# ProtectionAndShunt.net
KiCad netlist of a schematic drawn in Altium Designer
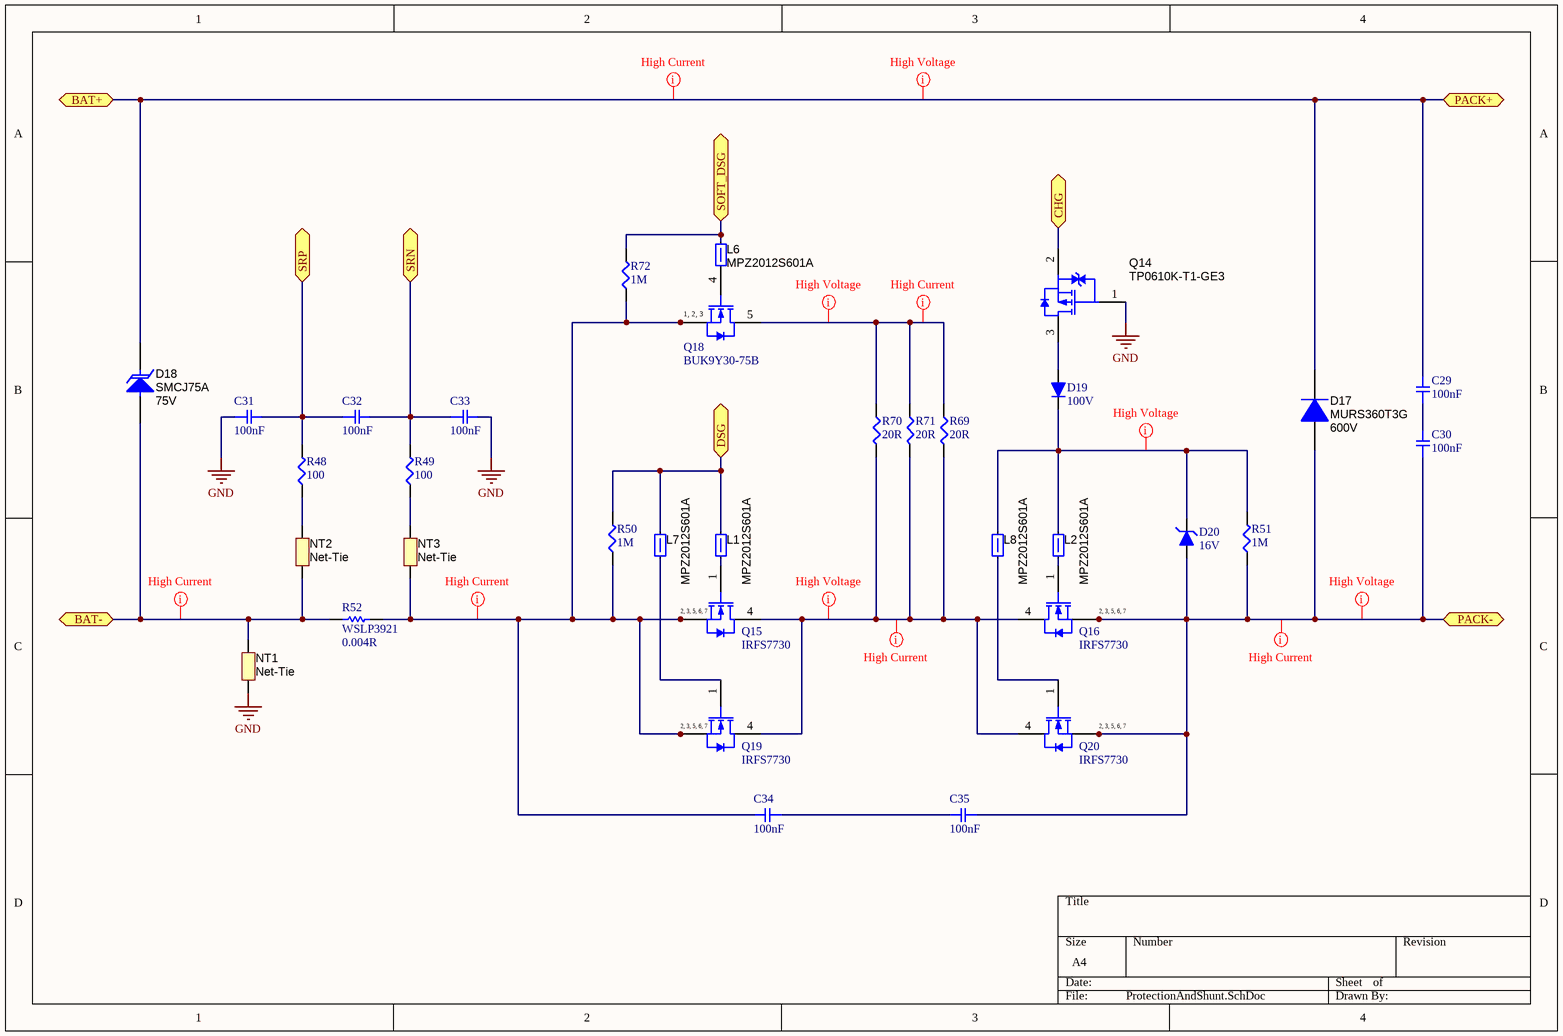
[diagram p0: ProtectionAndShunt.SchDoc]

(export (version "E")
  (design (tool "Eeschema 10.0.6"))
  (components
    (comp (ref "C29")
      (value "100nF")
      (footprint "SMD-0603C")
      (description "CAP CER 0.1UF 16V X7R 0603")
      (fields
        (field (name "DIGI-KEY PART NUMBER") "490-5796-1-ND")
        (field (name "PART NUMBER") "GCJ188R71C104KA01D")
      )
      (libsource (lib "capacitor_murata_0603") (part "GCJ188R71C104KA01D"))
    )
    (comp (ref "C30")
      (value "100nF")
      (footprint "SMD-0603C")
      (description "CAP CER 0.1UF 16V X7R 0603")
      (fields
        (field (name "DIGI-KEY PART NUMBER") "490-5796-1-ND")
        (field (name "PART NUMBER") "GCJ188R71C104KA01D")
      )
      (libsource (lib "capacitor_murata_0603") (part "GCJ188R71C104KA01D"))
    )
    (comp (ref "C31")
      (value "100nF")
      (footprint "SMD-0603C")
      (description "CAP CER 0.1UF 16V X7R 0603")
      (fields
        (field (name "DIGI-KEY PART NUMBER") "490-5796-1-ND")
        (field (name "PART NUMBER") "GCJ188R71C104KA01D")
      )
      (libsource (lib "capacitor_murata_0603") (part "GCJ188R71C104KA01D"))
    )
    (comp (ref "C32")
      (value "100nF")
      (footprint "SMD-0603C")
      (description "CAP CER 0.1UF 16V X7R 0603")
      (fields
        (field (name "DIGI-KEY PART NUMBER") "490-5796-1-ND")
        (field (name "PART NUMBER") "GCJ188R71C104KA01D")
      )
      (libsource (lib "capacitor_murata_0603") (part "GCJ188R71C104KA01D"))
    )
    (comp (ref "C33")
      (value "100nF")
      (footprint "SMD-0603C")
      (description "CAP CER 0.1UF 16V X7R 0603")
      (fields
        (field (name "DIGI-KEY PART NUMBER") "490-5796-1-ND")
        (field (name "PART NUMBER") "GCJ188R71C104KA01D")
      )
      (libsource (lib "capacitor_murata_0603") (part "GCJ188R71C104KA01D"))
    )
    (comp (ref "C34")
      (value "100nF")
      (footprint "SMD-0603C")
      (description "CAP CER 0.1UF 16V X7R 0603")
      (fields
        (field (name "DIGI-KEY PART NUMBER") "490-5796-1-ND")
        (field (name "PART NUMBER") "GCJ188R71C104KA01D")
      )
      (libsource (lib "capacitor_murata_0603") (part "GCJ188R71C104KA01D"))
    )
    (comp (ref "C35")
      (value "100nF")
      (footprint "SMD-0603C")
      (description "CAP CER 0.1UF 16V X7R 0603")
      (fields
        (field (name "DIGI-KEY PART NUMBER") "490-5796-1-ND")
        (field (name "PART NUMBER") "GCJ188R71C104KA01D")
      )
      (libsource (lib "capacitor_murata_0603") (part "GCJ188R71C104KA01D"))
    )
    (comp (ref "D17")
      (value "MURS360T3G")
      (footprint "SMC")
      (description "Diode, Ultrafast, 600V, 3A, SMC")
      (fields
        (field (name "MANUFACTURER") "ON Semiconductor")
        (field (name "ALTIUM_VALUE") "600V")
        (field (name "PUBLISHER") "Texas Instruments")
      )
      (libsource (lib "Components") (part "MURS360T3G"))
    )
    (comp (ref "D18")
      (value "SMCJ75A")
      (footprint "SMC")
      (description "Diode, TVS, Uni, 75V, 1500W, SMC")
      (fields
        (field (name "MANUFACTURER") "Fairchild Semiconductor")
        (field (name "ALTIUM_VALUE") "75V")
        (field (name "PUBLISHER") "Texas Instruments")
      )
      (libsource (lib "Components") (part "SMCJ75A"))
    )
    (comp (ref "D19")
      (value "100V")
      (footprint "SOD-323")
      (description "Diode")
      (libsource (lib "Components") (part "DIODE"))
    )
    (comp (ref "D20")
      (value "16V")
      (footprint "SOD-323")
      (description "Zener Diode 16V")
      (libsource (lib "Components") (part "ZENER_16V"))
    )
    (comp (ref "L1")
      (value "MPZ2012S601A")
      (footprint "SMD-0805-RES")
      (description "Ferrite Bead")
      (fields
        (field (name "PARTNUMBER") "BLM18SG221TN1D")
        (field (name "MANUFACTURER") "MuRata")
        (field (name "PUBLISHER") "Texas Instruments")
      )
      (libsource (lib "") (part "BLM18SG221TN1D_1"))
    )
    (comp (ref "L2")
      (value "MPZ2012S601A")
      (footprint "SMD-0805-RES")
      (description "Ferrite Bead")
      (fields
        (field (name "PARTNUMBER") "BLM18SG221TN1D")
        (field (name "MANUFACTURER") "MuRata")
        (field (name "PUBLISHER") "Texas Instruments")
      )
      (libsource (lib "Components") (part "BLM18SG221TN1D"))
    )
    (comp (ref "L6")
      (value "MPZ2012S601A")
      (footprint "SMD-0805-RES")
      (description "Ferrite Bead")
      (fields
        (field (name "PARTNUMBER") "BLM18SG221TN1D")
        (field (name "MANUFACTURER") "MuRata")
        (field (name "PUBLISHER") "Texas Instruments")
      )
      (libsource (lib "") (part "BLM18SG221TN1D_1"))
    )
    (comp (ref "L7")
      (value "MPZ2012S601A")
      (footprint "SMD-0805-RES")
      (description "Ferrite Bead")
      (fields
        (field (name "PARTNUMBER") "BLM18SG221TN1D")
        (field (name "MANUFACTURER") "MuRata")
        (field (name "PUBLISHER") "Texas Instruments")
      )
      (libsource (lib "") (part "BLM18SG221TN1D_1"))
    )
    (comp (ref "L8")
      (value "MPZ2012S601A")
      (footprint "SMD-0805-RES")
      (description "Ferrite Bead")
      (fields
        (field (name "PARTNUMBER") "BLM18SG221TN1D")
        (field (name "MANUFACTURER") "MuRata")
        (field (name "PUBLISHER") "Texas Instruments")
      )
      (libsource (lib "Components") (part "BLM18SG221TN1D"))
    )
    (comp (ref "NT1")
      (value "Net-Tie")
      (footprint "Net-Tie_10mil")
      (description "Single point connection between nets.")
      (fields (field (name "SYMBOLCREATOR") "codlsc") (field (name "PUBLISHER") "Texas Instruments"))
      (libsource (lib "Components") (part "Net-Tie"))
    )
    (comp (ref "NT2")
      (value "Net-Tie")
      (footprint "Net-Tie_10mil")
      (description "Single point connection between nets.")
      (fields (field (name "SYMBOLCREATOR") "codlsc") (field (name "PUBLISHER") "Texas Instruments"))
      (libsource (lib "Components") (part "Net-Tie"))
    )
    (comp (ref "NT3")
      (value "Net-Tie")
      (footprint "Net-Tie_10mil")
      (description "Single point connection between nets.")
      (fields (field (name "SYMBOLCREATOR") "codlsc") (field (name "PUBLISHER") "Texas Instruments"))
      (libsource (lib "Components") (part "Net-Tie"))
    )
    (comp (ref "Q14")
      (value "TP0610K-T1-GE3")
      (footprint "SOT23-3")
      (description "MOSFET, P-CH, -60 V, -0.185 A, SOT-23")
      (fields
        (field (name "MANUFACTURER") "Vishay-Siliconix")
        (field (name "SYMBOLCREATOR") "a0411947")
        (field (name "PUBLISHER") "Texas Instruments")
      )
      (libsource (lib "Components") (part "TP0610K-T1-GE3"))
    )
    (comp (ref "Q15")
      (value "IRFS7730")
      (footprint "INF-PG-TO263-7-3_N")
      (description "OptiMOS-T Power-Transistor, 40 V VDS, 180 A ID, PG-TO263-7-3, Reel, Green")
      (fields (field (name "MANUFACTURER") "Infineon") (field (name "PARTNUMBER") "IPB180N04S3-02"))
      (libsource (lib "Infineon_Power_MOSFET") (part "IPB180N04S3-02"))
    )
    (comp (ref "Q16")
      (value "IRFS7730")
      (footprint "INF-PG-TO263-7-3_N")
      (description "OptiMOS-T Power-Transistor, 40 V VDS, 180 A ID, PG-TO263-7-3, Reel, Green")
      (fields (field (name "MANUFACTURER") "Infineon") (field (name "PARTNUMBER") "IPB180N04S3-02"))
      (libsource (lib "Infineon_Power_MOSFET") (part "IPB180N04S3-02"))
    )
    (comp (ref "Q18")
      (value "BUK9Y30-75B")
      (footprint "NXP-SOT669_N")
      (description "N-Channel TrenchMOS Logic Level FET, 75 V, 34 A, 5-Pin SOT669, Tape and Reel")
      (fields
        (field (name "MANUFACTURER") "NXP Semiconductors")
        (field (name "PARTNUMBER") "BUK9Y30-75B,115")
      )
      (libsource (lib "NXP Semiconductors Automotive MOSFETs") (part "BUK9Y30-75B,115"))
    )
    (comp (ref "Q19")
      (value "IRFS7730")
      (footprint "INF-PG-TO263-7-3_N")
      (description "OptiMOS-T Power-Transistor, 40 V VDS, 180 A ID, PG-TO263-7-3, Reel, Green")
      (fields (field (name "MANUFACTURER") "Infineon") (field (name "PARTNUMBER") "IPB180N04S3-02"))
      (libsource (lib "Infineon_Power_MOSFET") (part "IPB180N04S3-02"))
    )
    (comp (ref "Q20")
      (value "IRFS7730")
      (footprint "INF-PG-TO263-7-3_N")
      (description "OptiMOS-T Power-Transistor, 40 V VDS, 180 A ID, PG-TO263-7-3, Reel, Green")
      (fields (field (name "MANUFACTURER") "Infineon") (field (name "PARTNUMBER") "IPB180N04S3-02"))
      (libsource (lib "Infineon_Power_MOSFET") (part "IPB180N04S3-02"))
    )
    (comp (ref "R48")
      (value "100")
      (footprint "SMD-0603-RES")
      (description "RES SMD 100 OHM 1% 1/10W 0603")
      (fields (field (name "PART NUMBER") "ERJ-3EKF1000V") (field (name "DIGI-KEY PART NUMBER") "P100HCT-ND"))
      (libsource (lib "Panasonic_ERJ_0603") (part "ERJ-3EKF1000V"))
    )
    (comp (ref "R49")
      (value "100")
      (footprint "SMD-0603-RES")
      (description "RES SMD 100 OHM 1% 1/10W 0603")
      (fields (field (name "PART NUMBER") "ERJ-3EKF1000V") (field (name "DIGI-KEY PART NUMBER") "P100HCT-ND"))
      (libsource (lib "Panasonic_ERJ_0603") (part "ERJ-3EKF1000V"))
    )
    (comp (ref "R50")
      (value "1M")
      (footprint "SMD-0603-RES")
      (description "RES SMD 1M OHM 5% 1/10W 0603")
      (fields
        (field (name "PART NUMBER") "ERJ-3GEYJ105V")
        (field (name "DIGI-KEY PART NUMBER") "P1.0MGCT-ND")
      )
      (libsource (lib "Panasonic_ERJ_0603") (part "ERJ-3GEYJ105V"))
    )
    (comp (ref "R51")
      (value "1M")
      (footprint "SMD-0603-RES")
      (description "RES SMD 1M OHM 5% 1/10W 0603")
      (fields
        (field (name "PART NUMBER") "ERJ-3GEYJ105V")
        (field (name "DIGI-KEY PART NUMBER") "P1.0MGCT-ND")
      )
      (libsource (lib "Panasonic_ERJ_0603") (part "ERJ-3GEYJ105V"))
    )
    (comp (ref "R52")
      (value "WSLP3921")
      (footprint "WSLP3921")
      (fields (field (name "ALTIUM_VALUE") "0.004R"))
      (libsource (lib "Components") (part "WSLP3921"))
    )
    (comp (ref "R69")
      (value "20R")
      (footprint "SMD-1206-RES")
      (description "RES SMD 20 OHM 1% 1/4W 1206")
      (fields
        (field (name "PART NUMBER") "ERJ-8ENF20R0V")
        (field (name "DIGI-KEY PART NUMBER") "P20.0FCT-ND")
      )
      (libsource (lib "Panasonic_ERJ_1206") (part "ERJ-8ENF20R0V"))
    )
    (comp (ref "R70")
      (value "20R")
      (footprint "SMD-1206-RES")
      (description "RES SMD 20 OHM 1% 1/4W 1206")
      (fields
        (field (name "PART NUMBER") "ERJ-8ENF20R0V")
        (field (name "DIGI-KEY PART NUMBER") "P20.0FCT-ND")
      )
      (libsource (lib "Panasonic_ERJ_1206") (part "ERJ-8ENF20R0V"))
    )
    (comp (ref "R71")
      (value "20R")
      (footprint "SMD-1206-RES")
      (description "RES SMD 20 OHM 1% 1/4W 1206")
      (fields
        (field (name "PART NUMBER") "ERJ-8ENF20R0V")
        (field (name "DIGI-KEY PART NUMBER") "P20.0FCT-ND")
      )
      (libsource (lib "Panasonic_ERJ_1206") (part "ERJ-8ENF20R0V"))
    )
    (comp (ref "R72")
      (value "1M")
      (footprint "SMD-0603-RES")
      (description "RES SMD 1M OHM 5% 1/10W 0603")
      (fields
        (field (name "PART NUMBER") "ERJ-3GEYJ105V")
        (field (name "DIGI-KEY PART NUMBER") "P1.0MGCT-ND")
      )
      (libsource (lib "Panasonic_ERJ_0603") (part "ERJ-3GEYJ105V"))
    )
  )
  (nets
    (net (code "1") (name "/BAT+") (class "Default")
      (node (ref "C29") (pin "2") (pinfunction "2_2") (pintype "passive"))
      (node (ref "D17") (pin "1") (pinfunction "K_1") (pintype "passive"))
      (node (ref "D18") (pin "1") (pinfunction "K_1") (pintype "passive"))
    )
    (net (code "2") (name "/BAT-") (class "Default")
      (node (ref "D18") (pin "2") (pinfunction "A_2") (pintype "passive"))
      (node (ref "NT1") (pin "2") (pinfunction "2_2") (pintype "passive"))
      (node (ref "NT2") (pin "1") (pinfunction "1_1") (pintype "passive"))
      (node (ref "R52") (pin "1") (pinfunction "1_1") (pintype "passive"))
    )
    (net (code "3") (name "/CHG") (class "Default")
      (node (ref "Q14") (pin "2") (pinfunction "S_2") (pintype "passive"))
    )
    (net (code "4") (name "/DSG") (class "Default")
      (node (ref "L1") (pin "2") (pinfunction "2_2") (pintype "passive"))
      (node (ref "L7") (pin "2") (pinfunction "2_2") (pintype "passive"))
      (node (ref "R50") (pin "2") (pinfunction "2_2") (pintype "passive"))
    )
    (net (code "5") (name "/PACK-") (class "Default")
      (node (ref "C30") (pin "1") (pinfunction "1_1") (pintype "passive"))
      (node (ref "C35") (pin "1") (pinfunction "1_1") (pintype "passive"))
      (node (ref "D17") (pin "2") (pinfunction "A_2") (pintype "passive"))
      (node (ref "D20") (pin "2") (pinfunction "A_2") (pintype "passive"))
      (node (ref "Q16") (pin "2") (pinfunction "SOURCE_2") (pintype "passive"))
      (node (ref "Q16") (pin "3") (pinfunction "SOURCE_3") (pintype "passive"))
      (node (ref "Q16") (pin "5") (pinfunction "SOURCE_5") (pintype "passive"))
      (node (ref "Q16") (pin "6") (pinfunction "SOURCE_6") (pintype "passive"))
      (node (ref "Q16") (pin "7") (pinfunction "SOURCE_7") (pintype "passive"))
      (node (ref "Q20") (pin "2") (pinfunction "SOURCE_2") (pintype "passive"))
      (node (ref "Q20") (pin "3") (pinfunction "SOURCE_3") (pintype "passive"))
      (node (ref "Q20") (pin "5") (pinfunction "SOURCE_5") (pintype "passive"))
      (node (ref "Q20") (pin "6") (pinfunction "SOURCE_6") (pintype "passive"))
      (node (ref "Q20") (pin "7") (pinfunction "SOURCE_7") (pintype "passive"))
      (node (ref "R51") (pin "1") (pinfunction "1_1") (pintype "passive"))
    )
    (net (code "6") (name "/SOFT_DSG") (class "Default")
      (node (ref "L6") (pin "2") (pinfunction "2_2") (pintype "passive"))
      (node (ref "R72") (pin "2") (pinfunction "2_2") (pintype "passive"))
    )
    (net (code "7") (name "/SRN") (class "Default")
      (node (ref "C32") (pin "2") (pinfunction "2_2") (pintype "passive"))
      (node (ref "C33") (pin "1") (pinfunction "1_1") (pintype "passive"))
      (node (ref "R49") (pin "2") (pinfunction "2_2") (pintype "passive"))
    )
    (net (code "8") (name "/SRP") (class "Default")
      (node (ref "C31") (pin "2") (pinfunction "2_2") (pintype "passive"))
      (node (ref "C32") (pin "1") (pinfunction "1_1") (pintype "passive"))
      (node (ref "R48") (pin "2") (pinfunction "2_2") (pintype "passive"))
    )
    (net (code "9") (name "GND") (class "Default")
      (node (ref "C31") (pin "1") (pinfunction "1_1") (pintype "passive"))
      (node (ref "C33") (pin "2") (pinfunction "2_2") (pintype "passive"))
      (node (ref "NT1") (pin "1") (pinfunction "1_1") (pintype "passive"))
      (node (ref "Q14") (pin "1") (pinfunction "G_1") (pintype "passive"))
    )
    (net (code "10") (name "Net-(C29-Pad1)") (class "Default")
      (node (ref "C29") (pin "1") (pinfunction "1_1") (pintype "passive"))
      (node (ref "C30") (pin "2") (pinfunction "2_2") (pintype "passive"))
    )
    (net (code "11") (name "Net-(C34-Pad1)") (class "Default")
      (node (ref "C34") (pin "1") (pinfunction "1_1") (pintype "passive"))
      (node (ref "C35") (pin "2") (pinfunction "2_2") (pintype "passive"))
    )
    (net (code "12") (name "Net-(C34-Pad2)") (class "Default")
      (node (ref "C34") (pin "2") (pinfunction "2_2") (pintype "passive"))
      (node (ref "NT3") (pin "1") (pinfunction "1_1") (pintype "passive"))
      (node (ref "Q15") (pin "2") (pinfunction "SOURCE_2") (pintype "passive"))
      (node (ref "Q15") (pin "3") (pinfunction "SOURCE_3") (pintype "passive"))
      (node (ref "Q15") (pin "5") (pinfunction "SOURCE_5") (pintype "passive"))
      (node (ref "Q15") (pin "6") (pinfunction "SOURCE_6") (pintype "passive"))
      (node (ref "Q15") (pin "7") (pinfunction "SOURCE_7") (pintype "passive"))
      (node (ref "Q18") (pin "1") (pinfunction "S_1") (pintype "passive"))
      (node (ref "Q18") (pin "2") (pinfunction "S_2") (pintype "passive"))
      (node (ref "Q18") (pin "3") (pinfunction "S_3") (pintype "passive"))
      (node (ref "Q19") (pin "2") (pinfunction "SOURCE_2") (pintype "passive"))
      (node (ref "Q19") (pin "3") (pinfunction "SOURCE_3") (pintype "passive"))
      (node (ref "Q19") (pin "5") (pinfunction "SOURCE_5") (pintype "passive"))
      (node (ref "Q19") (pin "6") (pinfunction "SOURCE_6") (pintype "passive"))
      (node (ref "Q19") (pin "7") (pinfunction "SOURCE_7") (pintype "passive"))
      (node (ref "R50") (pin "1") (pinfunction "1_1") (pintype "passive"))
      (node (ref "R52") (pin "2") (pinfunction "2_2") (pintype "passive"))
      (node (ref "R72") (pin "1") (pinfunction "1_1") (pintype "passive"))
    )
    (net (code "13") (name "Net-(D19-A)") (class "Default")
      (node (ref "D19") (pin "2") (pinfunction "A_2") (pintype "passive"))
      (node (ref "Q14") (pin "3") (pinfunction "D_3") (pintype "passive"))
    )
    (net (code "14") (name "Net-(D19-K)") (class "Default")
      (node (ref "D19") (pin "1") (pinfunction "K_1") (pintype "passive"))
      (node (ref "D20") (pin "1") (pinfunction "K_1") (pintype "passive"))
      (node (ref "L2") (pin "2") (pinfunction "2_2") (pintype "passive"))
      (node (ref "L8") (pin "2") (pinfunction "2_2") (pintype "passive"))
      (node (ref "R51") (pin "2") (pinfunction "2_2") (pintype "passive"))
    )
    (net (code "15") (name "Net-(NT2-Pad2)") (class "Default")
      (node (ref "NT2") (pin "2") (pinfunction "2_2") (pintype "passive"))
      (node (ref "R48") (pin "1") (pinfunction "1_1") (pintype "passive"))
    )
    (net (code "16") (name "Net-(NT3-Pad2)") (class "Default")
      (node (ref "NT3") (pin "2") (pinfunction "2_2") (pintype "passive"))
      (node (ref "R49") (pin "1") (pinfunction "1_1") (pintype "passive"))
    )
    (net (code "17") (name "Net-(Q15-DRAIN)") (class "Default")
      (node (ref "Q15") (pin "4") (pinfunction "DRAIN_4") (pintype "passive"))
      (node (ref "Q16") (pin "4") (pinfunction "DRAIN_4") (pintype "passive"))
      (node (ref "Q19") (pin "4") (pinfunction "DRAIN_4") (pintype "passive"))
      (node (ref "Q20") (pin "4") (pinfunction "DRAIN_4") (pintype "passive"))
      (node (ref "R69") (pin "2") (pinfunction "2_2") (pintype "passive"))
      (node (ref "R70") (pin "2") (pinfunction "2_2") (pintype "passive"))
      (node (ref "R71") (pin "2") (pinfunction "2_2") (pintype "passive"))
    )
    (net (code "18") (name "Net-(Q15-GATE)") (class "Default")
      (node (ref "L1") (pin "1") (pinfunction "1_1") (pintype "passive"))
      (node (ref "Q15") (pin "1") (pinfunction "GATE_1") (pintype "passive"))
    )
    (net (code "19") (name "Net-(Q16-GATE)") (class "Default")
      (node (ref "L2") (pin "1") (pinfunction "1_1") (pintype "passive"))
      (node (ref "Q16") (pin "1") (pinfunction "GATE_1") (pintype "passive"))
    )
    (net (code "20") (name "Net-(Q18-D)") (class "Default")
      (node (ref "Q18") (pin "5") (pinfunction "D_5") (pintype "passive"))
      (node (ref "R69") (pin "1") (pinfunction "1_1") (pintype "passive"))
      (node (ref "R70") (pin "1") (pinfunction "1_1") (pintype "passive"))
      (node (ref "R71") (pin "1") (pinfunction "1_1") (pintype "passive"))
    )
    (net (code "21") (name "Net-(Q18-G)") (class "Default")
      (node (ref "L6") (pin "1") (pinfunction "1_1") (pintype "passive"))
      (node (ref "Q18") (pin "4") (pinfunction "G_4") (pintype "passive"))
    )
    (net (code "22") (name "Net-(Q19-GATE)") (class "Default")
      (node (ref "L7") (pin "1") (pinfunction "1_1") (pintype "passive"))
      (node (ref "Q19") (pin "1") (pinfunction "GATE_1") (pintype "passive"))
    )
    (net (code "23") (name "Net-(Q20-GATE)") (class "Default")
      (node (ref "L8") (pin "1") (pinfunction "1_1") (pintype "passive"))
      (node (ref "Q20") (pin "1") (pinfunction "GATE_1") (pintype "passive"))
    )
  )
)
